# ESC_Power.net
KiCad netlist of a schematic drawn in Altium Designer
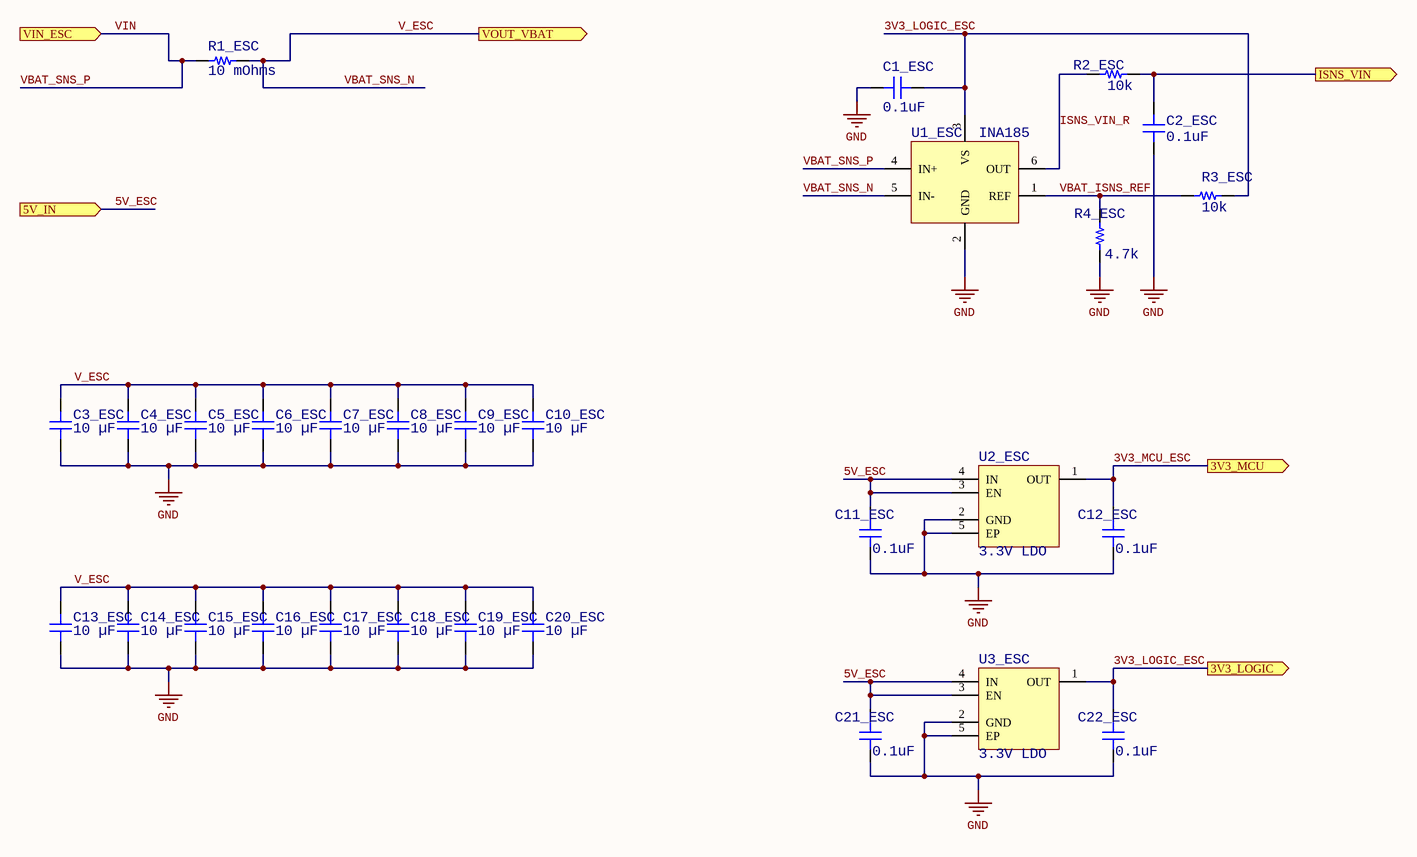
[diagram p0: ESC_Power.SchDoc]

(export (version "E")
  (design (tool "Eeschema 10.0.6"))
  (components
    (comp (ref "C1_ESC")
      (value "0.1uF")
      (footprint "CAP_0402")
      (description "CAP CER 402")
      (libsource (lib "IC") (part "CAP_0402"))
    )
    (comp (ref "C2_ESC")
      (value "0.1uF")
      (footprint "CAP_0402")
      (description "CAP CER 402")
      (libsource (lib "IC") (part "CAP_0402"))
    )
    (comp (ref "C3_ESC")
      (value "10 µF")
      (footprint "CAP 1206_3216 - 0.8MM")
      (description "CAP CER 10UF 25V X6S 1206")
      (fields
        (field (name "PART NUMBER") "CL31X106KAHNNNE")
        (field (name "MANUFACTURER") "Samsung Electro-Mechanics")
      )
      (libsource (lib "Celestial Altium Library - altium_library") (part "Capacitor"))
    )
    (comp (ref "C4_ESC")
      (value "10 µF")
      (footprint "CAP 1206_3216 - 0.8MM")
      (description "CAP CER 10UF 25V X6S 1206")
      (fields
        (field (name "PART NUMBER") "CL31X106KAHNNNE")
        (field (name "MANUFACTURER") "Samsung Electro-Mechanics")
      )
      (libsource (lib "Celestial Altium Library - altium_library") (part "Capacitor"))
    )
    (comp (ref "C5_ESC")
      (value "10 µF")
      (footprint "CAP 1206_3216 - 0.8MM")
      (description "CAP CER 10UF 25V X6S 1206")
      (fields
        (field (name "PART NUMBER") "CL31X106KAHNNNE")
        (field (name "MANUFACTURER") "Samsung Electro-Mechanics")
      )
      (libsource (lib "Celestial Altium Library - altium_library") (part "Capacitor"))
    )
    (comp (ref "C6_ESC")
      (value "10 µF")
      (footprint "CAP 1206_3216 - 0.8MM")
      (description "CAP CER 10UF 25V X6S 1206")
      (fields
        (field (name "PART NUMBER") "CL31X106KAHNNNE")
        (field (name "MANUFACTURER") "Samsung Electro-Mechanics")
      )
      (libsource (lib "Celestial Altium Library - altium_library") (part "Capacitor"))
    )
    (comp (ref "C7_ESC")
      (value "10 µF")
      (footprint "CAP 1206_3216 - 0.8MM")
      (description "CAP CER 10UF 25V X6S 1206")
      (fields
        (field (name "PART NUMBER") "CL31X106KAHNNNE")
        (field (name "MANUFACTURER") "Samsung Electro-Mechanics")
      )
      (libsource (lib "Celestial Altium Library - altium_library") (part "Capacitor"))
    )
    (comp (ref "C8_ESC")
      (value "10 µF")
      (footprint "CAP 1206_3216 - 0.8MM")
      (description "CAP CER 10UF 25V X6S 1206")
      (fields
        (field (name "PART NUMBER") "CL31X106KAHNNNE")
        (field (name "MANUFACTURER") "Samsung Electro-Mechanics")
      )
      (libsource (lib "Celestial Altium Library - altium_library") (part "Capacitor"))
    )
    (comp (ref "C9_ESC")
      (value "10 µF")
      (footprint "CAP 1206_3216 - 0.8MM")
      (description "CAP CER 10UF 25V X6S 1206")
      (fields
        (field (name "PART NUMBER") "CL31X106KAHNNNE")
        (field (name "MANUFACTURER") "Samsung Electro-Mechanics")
      )
      (libsource (lib "Celestial Altium Library - altium_library") (part "Capacitor"))
    )
    (comp (ref "C10_ESC")
      (value "10 µF")
      (footprint "CAP 1206_3216 - 0.8MM")
      (description "CAP CER 10UF 25V X6S 1206")
      (fields
        (field (name "PART NUMBER") "CL31X106KAHNNNE")
        (field (name "MANUFACTURER") "Samsung Electro-Mechanics")
      )
      (libsource (lib "Celestial Altium Library - altium_library") (part "Capacitor"))
    )
    (comp (ref "C11_ESC")
      (value "0.1uF")
      (footprint "CAP_0402")
      (description "CAP CER 402")
      (libsource (lib "IC") (part "CAP_0402"))
    )
    (comp (ref "C12_ESC")
      (value "0.1uF")
      (footprint "CAP_0402")
      (description "CAP CER 402")
      (libsource (lib "IC") (part "CAP_0402"))
    )
    (comp (ref "C13_ESC")
      (value "10 µF")
      (footprint "CAP 1206_3216 - 0.8MM")
      (description "CAP CER 10UF 25V X6S 1206")
      (fields
        (field (name "PART NUMBER") "CL31X106KAHNNNE")
        (field (name "MANUFACTURER") "Samsung Electro-Mechanics")
      )
      (libsource (lib "Celestial Altium Library - altium_library") (part "Capacitor"))
    )
    (comp (ref "C14_ESC")
      (value "10 µF")
      (footprint "CAP 1206_3216 - 0.8MM")
      (description "CAP CER 10UF 25V X6S 1206")
      (fields
        (field (name "PART NUMBER") "CL31X106KAHNNNE")
        (field (name "MANUFACTURER") "Samsung Electro-Mechanics")
      )
      (libsource (lib "Celestial Altium Library - altium_library") (part "Capacitor"))
    )
    (comp (ref "C15_ESC")
      (value "10 µF")
      (footprint "CAP 1206_3216 - 0.8MM")
      (description "CAP CER 10UF 25V X6S 1206")
      (fields
        (field (name "PART NUMBER") "CL31X106KAHNNNE")
        (field (name "MANUFACTURER") "Samsung Electro-Mechanics")
      )
      (libsource (lib "Celestial Altium Library - altium_library") (part "Capacitor"))
    )
    (comp (ref "C16_ESC")
      (value "10 µF")
      (footprint "CAP 1206_3216 - 0.8MM")
      (description "CAP CER 10UF 25V X6S 1206")
      (fields
        (field (name "PART NUMBER") "CL31X106KAHNNNE")
        (field (name "MANUFACTURER") "Samsung Electro-Mechanics")
      )
      (libsource (lib "Celestial Altium Library - altium_library") (part "Capacitor"))
    )
    (comp (ref "C17_ESC")
      (value "10 µF")
      (footprint "CAP 1206_3216 - 0.8MM")
      (description "CAP CER 10UF 25V X6S 1206")
      (fields
        (field (name "PART NUMBER") "CL31X106KAHNNNE")
        (field (name "MANUFACTURER") "Samsung Electro-Mechanics")
      )
      (libsource (lib "Celestial Altium Library - altium_library") (part "Capacitor"))
    )
    (comp (ref "C18_ESC")
      (value "10 µF")
      (footprint "CAP 1206_3216 - 0.8MM")
      (description "CAP CER 10UF 25V X6S 1206")
      (fields
        (field (name "PART NUMBER") "CL31X106KAHNNNE")
        (field (name "MANUFACTURER") "Samsung Electro-Mechanics")
      )
      (libsource (lib "Celestial Altium Library - altium_library") (part "Capacitor"))
    )
    (comp (ref "C19_ESC")
      (value "10 µF")
      (footprint "CAP 1206_3216 - 0.8MM")
      (description "CAP CER 10UF 25V X6S 1206")
      (fields
        (field (name "PART NUMBER") "CL31X106KAHNNNE")
        (field (name "MANUFACTURER") "Samsung Electro-Mechanics")
      )
      (libsource (lib "Celestial Altium Library - altium_library") (part "Capacitor"))
    )
    (comp (ref "C20_ESC")
      (value "10 µF")
      (footprint "CAP 1206_3216 - 0.8MM")
      (description "CAP CER 10UF 25V X6S 1206")
      (fields
        (field (name "PART NUMBER") "CL31X106KAHNNNE")
        (field (name "MANUFACTURER") "Samsung Electro-Mechanics")
      )
      (libsource (lib "Celestial Altium Library - altium_library") (part "Capacitor"))
    )
    (comp (ref "C21_ESC")
      (value "0.1uF")
      (footprint "CAP_0402")
      (description "CAP CER 402")
      (libsource (lib "IC") (part "CAP_0402"))
    )
    (comp (ref "C22_ESC")
      (value "0.1uF")
      (footprint "CAP_0402")
      (description "CAP CER 402")
      (libsource (lib "IC") (part "CAP_0402"))
    )
    (comp (ref "R1_ESC")
      (value "10 mOhms")
      (footprint "RES 1206_3216")
      (description "RES 0.039 OHM 1% 3/4W 1206")
      (fields (field (name "PART NUMBER") "KRL1632E-M-R039-F-T5") (field (name "MANUFACTURER") "Susumu"))
      (libsource (lib "Celestial Altium Library - altium_library") (part "Resistor"))
    )
    (comp (ref "R2_ESC")
      (value "10k")
      (footprint "RES_0402")
      (description "RES 0402")
      (libsource (lib "IC") (part "RES_0402"))
    )
    (comp (ref "R3_ESC")
      (value "10k")
      (footprint "RES_0402")
      (description "RES 0402")
      (libsource (lib "IC") (part "RES_0402"))
    )
    (comp (ref "R4_ESC")
      (value "4.7k")
      (footprint "RES_0402")
      (description "RES 0402")
      (libsource (lib "IC") (part "RES_0402"))
    )
    (comp (ref "U1_ESC")
      (value "INA185")
      (footprint "TI SC70-6 DCK")
      (description "INA185A2")
      (libsource (lib "IC") (part "INA185"))
    )
    (comp (ref "U2_ESC")
      (value "3.3V LDO")
      (footprint "XDFN-4")
      (libsource (lib "IC") (part "TLV74033PDQNR"))
    )
    (comp (ref "U3_ESC")
      (value "3.3V LDO")
      (footprint "XDFN-4")
      (libsource (lib "IC") (part "TLV74033PDQNR"))
    )
  )
  (nets
    (net (code "1") (name "/3V3_LOGIC_ESC") (class "Default")
      (node (ref "C1_ESC") (pin "1") (pinfunction "1_1") (pintype "passive"))
      (node (ref "C22_ESC") (pin "2") (pinfunction "2_2") (pintype "passive"))
      (node (ref "R3_ESC") (pin "1") (pinfunction "1_1") (pintype "passive"))
      (node (ref "U1_ESC") (pin "3") (pinfunction "VS_3") (pintype "passive"))
      (node (ref "U3_ESC") (pin "1") (pinfunction "OUT_1") (pintype "passive"))
    )
    (net (code "2") (name "/3V3_MCU_ESC") (class "Default")
      (node (ref "C12_ESC") (pin "2") (pinfunction "2_2") (pintype "passive"))
      (node (ref "U2_ESC") (pin "1") (pinfunction "OUT_1") (pintype "passive"))
    )
    (net (code "3") (name "/5V_ESC") (class "Default")
      (node (ref "C11_ESC") (pin "2") (pinfunction "2_2") (pintype "passive"))
      (node (ref "C21_ESC") (pin "2") (pinfunction "2_2") (pintype "passive"))
      (node (ref "U2_ESC") (pin "3") (pinfunction "EN_3") (pintype "passive"))
      (node (ref "U2_ESC") (pin "4") (pinfunction "IN_4") (pintype "passive"))
      (node (ref "U3_ESC") (pin "3") (pinfunction "EN_3") (pintype "passive"))
      (node (ref "U3_ESC") (pin "4") (pinfunction "IN_4") (pintype "passive"))
    )
    (net (code "4") (name "/ISNS_VIN") (class "Default")
      (node (ref "C2_ESC") (pin "1") (pinfunction "1_1") (pintype "passive"))
      (node (ref "R2_ESC") (pin "1") (pinfunction "1_1") (pintype "passive"))
    )
    (net (code "5") (name "/ISNS_VIN_R") (class "Default")
      (node (ref "R2_ESC") (pin "2") (pinfunction "2_2") (pintype "passive"))
      (node (ref "U1_ESC") (pin "6") (pinfunction "OUT_6") (pintype "passive"))
    )
    (net (code "6") (name "/VBAT_ISNS_REF") (class "Default")
      (node (ref "R3_ESC") (pin "2") (pinfunction "2_2") (pintype "passive"))
      (node (ref "R4_ESC") (pin "1") (pinfunction "1_1") (pintype "passive"))
      (node (ref "U1_ESC") (pin "1") (pinfunction "REF_1") (pintype "passive"))
    )
    (net (code "7") (name "/VBAT_SNS_N") (class "Default")
      (node (ref "C10_ESC") (pin "2") (pinfunction "2_2") (pintype "passive"))
      (node (ref "C13_ESC") (pin "2") (pinfunction "2_2") (pintype "passive"))
      (node (ref "C14_ESC") (pin "2") (pinfunction "2_2") (pintype "passive"))
      (node (ref "C15_ESC") (pin "2") (pinfunction "2_2") (pintype "passive"))
      (node (ref "C16_ESC") (pin "2") (pinfunction "2_2") (pintype "passive"))
      (node (ref "C17_ESC") (pin "2") (pinfunction "2_2") (pintype "passive"))
      (node (ref "C18_ESC") (pin "2") (pinfunction "2_2") (pintype "passive"))
      (node (ref "C19_ESC") (pin "2") (pinfunction "2_2") (pintype "passive"))
      (node (ref "C20_ESC") (pin "2") (pinfunction "2_2") (pintype "passive"))
      (node (ref "C3_ESC") (pin "2") (pinfunction "2_2") (pintype "passive"))
      (node (ref "C4_ESC") (pin "2") (pinfunction "2_2") (pintype "passive"))
      (node (ref "C5_ESC") (pin "2") (pinfunction "2_2") (pintype "passive"))
      (node (ref "C6_ESC") (pin "2") (pinfunction "2_2") (pintype "passive"))
      (node (ref "C7_ESC") (pin "2") (pinfunction "2_2") (pintype "passive"))
      (node (ref "C8_ESC") (pin "2") (pinfunction "2_2") (pintype "passive"))
      (node (ref "C9_ESC") (pin "2") (pinfunction "2_2") (pintype "passive"))
      (node (ref "R1_ESC") (pin "2") (pinfunction "2_2") (pintype "passive"))
      (node (ref "U1_ESC") (pin "5") (pinfunction "IN-_5") (pintype "passive"))
    )
    (net (code "8") (name "/VBAT_SNS_P") (class "Default")
      (node (ref "R1_ESC") (pin "1") (pinfunction "1_1") (pintype "passive"))
      (node (ref "U1_ESC") (pin "4") (pinfunction "IN+_4") (pintype "passive"))
    )
    (net (code "9") (name "GND") (class "Default")
      (node (ref "C10_ESC") (pin "1") (pinfunction "1_1") (pintype "passive"))
      (node (ref "C11_ESC") (pin "1") (pinfunction "1_1") (pintype "passive"))
      (node (ref "C12_ESC") (pin "1") (pinfunction "1_1") (pintype "passive"))
      (node (ref "C13_ESC") (pin "1") (pinfunction "1_1") (pintype "passive"))
      (node (ref "C14_ESC") (pin "1") (pinfunction "1_1") (pintype "passive"))
      (node (ref "C15_ESC") (pin "1") (pinfunction "1_1") (pintype "passive"))
      (node (ref "C16_ESC") (pin "1") (pinfunction "1_1") (pintype "passive"))
      (node (ref "C17_ESC") (pin "1") (pinfunction "1_1") (pintype "passive"))
      (node (ref "C18_ESC") (pin "1") (pinfunction "1_1") (pintype "passive"))
      (node (ref "C19_ESC") (pin "1") (pinfunction "1_1") (pintype "passive"))
      (node (ref "C1_ESC") (pin "2") (pinfunction "2_2") (pintype "passive"))
      (node (ref "C20_ESC") (pin "1") (pinfunction "1_1") (pintype "passive"))
      (node (ref "C21_ESC") (pin "1") (pinfunction "1_1") (pintype "passive"))
      (node (ref "C22_ESC") (pin "1") (pinfunction "1_1") (pintype "passive"))
      (node (ref "C2_ESC") (pin "2") (pinfunction "2_2") (pintype "passive"))
      (node (ref "C3_ESC") (pin "1") (pinfunction "1_1") (pintype "passive"))
      (node (ref "C4_ESC") (pin "1") (pinfunction "1_1") (pintype "passive"))
      (node (ref "C5_ESC") (pin "1") (pinfunction "1_1") (pintype "passive"))
      (node (ref "C6_ESC") (pin "1") (pinfunction "1_1") (pintype "passive"))
      (node (ref "C7_ESC") (pin "1") (pinfunction "1_1") (pintype "passive"))
      (node (ref "C8_ESC") (pin "1") (pinfunction "1_1") (pintype "passive"))
      (node (ref "C9_ESC") (pin "1") (pinfunction "1_1") (pintype "passive"))
      (node (ref "R4_ESC") (pin "2") (pinfunction "2_2") (pintype "passive"))
      (node (ref "U1_ESC") (pin "2") (pinfunction "GND_2") (pintype "passive"))
      (node (ref "U2_ESC") (pin "2") (pinfunction "GND_2") (pintype "passive"))
      (node (ref "U2_ESC") (pin "5") (pinfunction "EP_5") (pintype "passive"))
      (node (ref "U3_ESC") (pin "2") (pinfunction "GND_2") (pintype "passive"))
      (node (ref "U3_ESC") (pin "5") (pinfunction "EP_5") (pintype "passive"))
    )
  )
)
